# blank.net
KiCad netlist of a schematic drawn in EAGLE
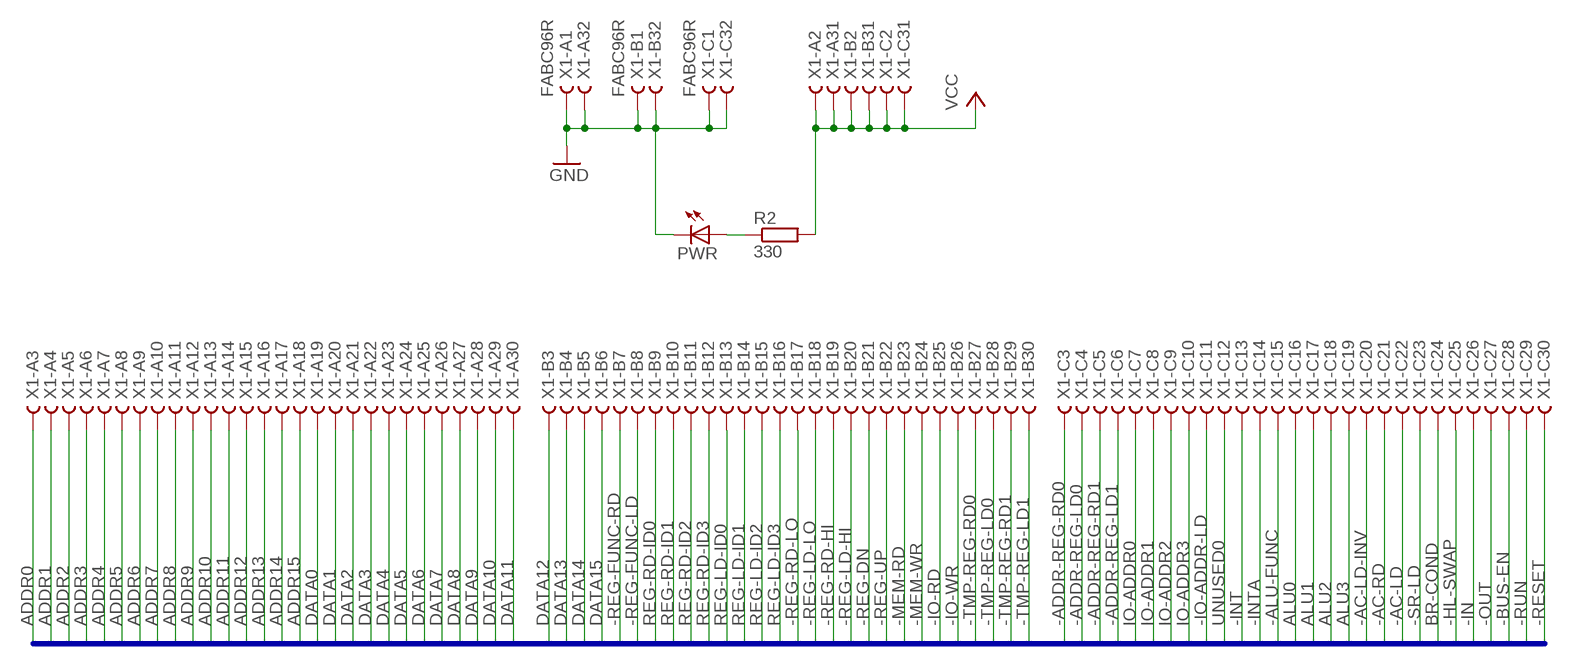
[diagram p0: schematic, sheet 1]

(export (version "E")
  (design (tool "Eeschema 10.0.6"))
  (components
    (comp (ref "PWR")
      (value "LED5MM")
      (footprint "eagle-import:LED5MM")
      (libsource (lib "eagle-import") (part "LED5MM"))
    )
    (comp (ref "R2")
      (value "330")
      (footprint "eagle-import:0207_10")
      (libsource (lib "eagle-import") (part "R0207/10"))
    )
    (comp (ref "X1")
      (value "FABC96R")
      (footprint "eagle-import:FABC96R")
      (libsource (lib "eagle-import") (part "FABC96R"))
    )
  )
  (nets
    (net (code "1") (name "/-AC-LD") (class "Default")
      (node (ref "X1") (pin "C22") (pinfunction "B_C22") (pintype "passive"))
    )
    (net (code "2") (name "/-AC-LD-INV") (class "Default")
      (node (ref "X1") (pin "C20") (pinfunction "B_C20") (pintype "passive"))
    )
    (net (code "3") (name "/-AC-RD") (class "Default")
      (node (ref "X1") (pin "C21") (pinfunction "B_C21") (pintype "passive"))
    )
    (net (code "4") (name "/-ADDR-REG-LD0") (class "Default")
      (node (ref "X1") (pin "C4") (pinfunction "B_C4") (pintype "passive"))
    )
    (net (code "5") (name "/-ADDR-REG-LD1") (class "Default")
      (node (ref "X1") (pin "C6") (pinfunction "B_C6") (pintype "passive"))
    )
    (net (code "6") (name "/-ADDR-REG-RD0") (class "Default")
      (node (ref "X1") (pin "C3") (pinfunction "B_C3") (pintype "passive"))
    )
    (net (code "7") (name "/-ADDR-REG-RD1") (class "Default")
      (node (ref "X1") (pin "C5") (pinfunction "B_C5") (pintype "passive"))
    )
    (net (code "8") (name "/-ALU-FUNC") (class "Default")
      (node (ref "X1") (pin "C15") (pinfunction "B_C15") (pintype "passive"))
    )
    (net (code "9") (name "/-BUS-EN") (class "Default")
      (node (ref "X1") (pin "C28") (pinfunction "B_C28") (pintype "passive"))
    )
    (net (code "10") (name "/-HL-SWAP") (class "Default")
      (node (ref "X1") (pin "C25") (pinfunction "B_C25") (pintype "passive"))
    )
    (net (code "11") (name "/-IN") (class "Default")
      (node (ref "X1") (pin "C26") (pinfunction "B_C26") (pintype "passive"))
    )
    (net (code "12") (name "/-INT") (class "Default")
      (node (ref "X1") (pin "C13") (pinfunction "B_C13") (pintype "passive"))
    )
    (net (code "13") (name "/-INTA") (class "Default")
      (node (ref "X1") (pin "C14") (pinfunction "B_C14") (pintype "passive"))
    )
    (net (code "14") (name "/-IO-ADDR-LD") (class "Default")
      (node (ref "X1") (pin "C11") (pinfunction "B_C11") (pintype "passive"))
    )
    (net (code "15") (name "/-IO-RD") (class "Default")
      (node (ref "X1") (pin "B25") (pinfunction "B_B25") (pintype "passive"))
    )
    (net (code "16") (name "/-IO-WR") (class "Default")
      (node (ref "X1") (pin "B26") (pinfunction "B_B26") (pintype "passive"))
    )
    (net (code "17") (name "/-MEM-RD") (class "Default")
      (node (ref "X1") (pin "B23") (pinfunction "B_B23") (pintype "passive"))
    )
    (net (code "18") (name "/-MEM-WR") (class "Default")
      (node (ref "X1") (pin "B24") (pinfunction "B_B24") (pintype "passive"))
    )
    (net (code "19") (name "/-OUT") (class "Default")
      (node (ref "X1") (pin "C27") (pinfunction "B_C27") (pintype "passive"))
    )
    (net (code "20") (name "/-REG-DN") (class "Default")
      (node (ref "X1") (pin "B21") (pinfunction "B_B21") (pintype "passive"))
    )
    (net (code "21") (name "/-REG-FUNC-LD") (class "Default")
      (node (ref "X1") (pin "B8") (pinfunction "B_B8") (pintype "passive"))
    )
    (net (code "22") (name "/-REG-FUNC-RD") (class "Default")
      (node (ref "X1") (pin "B7") (pinfunction "B_B7") (pintype "passive"))
    )
    (net (code "23") (name "/-REG-LD-HI") (class "Default")
      (node (ref "X1") (pin "B20") (pinfunction "B_B20") (pintype "passive"))
    )
    (net (code "24") (name "/-REG-LD-LO") (class "Default")
      (node (ref "X1") (pin "B18") (pinfunction "B_B18") (pintype "passive"))
    )
    (net (code "25") (name "/-REG-RD-HI") (class "Default")
      (node (ref "X1") (pin "B19") (pinfunction "B_B19") (pintype "passive"))
    )
    (net (code "26") (name "/-REG-RD-LO") (class "Default")
      (node (ref "X1") (pin "B17") (pinfunction "B_B17") (pintype "passive"))
    )
    (net (code "27") (name "/-REG-UP") (class "Default")
      (node (ref "X1") (pin "B22") (pinfunction "B_B22") (pintype "passive"))
    )
    (net (code "28") (name "/-RESET") (class "Default")
      (node (ref "X1") (pin "C30") (pinfunction "B_C30") (pintype "passive"))
    )
    (net (code "29") (name "/-RUN") (class "Default")
      (node (ref "X1") (pin "C29") (pinfunction "B_C29") (pintype "passive"))
    )
    (net (code "30") (name "/-SR-LD") (class "Default")
      (node (ref "X1") (pin "C23") (pinfunction "B_C23") (pintype "passive"))
    )
    (net (code "31") (name "/-TMP-REG-LD0") (class "Default")
      (node (ref "X1") (pin "B28") (pinfunction "B_B28") (pintype "passive"))
    )
    (net (code "32") (name "/-TMP-REG-LD1") (class "Default")
      (node (ref "X1") (pin "B30") (pinfunction "B_B30") (pintype "passive"))
    )
    (net (code "33") (name "/-TMP-REG-RD0") (class "Default")
      (node (ref "X1") (pin "B27") (pinfunction "B_B27") (pintype "passive"))
    )
    (net (code "34") (name "/-TMP-REG-RD1") (class "Default")
      (node (ref "X1") (pin "B29") (pinfunction "B_B29") (pintype "passive"))
    )
    (net (code "35") (name "/ADDR0") (class "Default")
      (node (ref "X1") (pin "A3") (pinfunction "B_A3") (pintype "passive"))
    )
    (net (code "36") (name "/ADDR1") (class "Default")
      (node (ref "X1") (pin "A4") (pinfunction "B_A4") (pintype "passive"))
    )
    (net (code "37") (name "/ADDR2") (class "Default")
      (node (ref "X1") (pin "A5") (pinfunction "B_A5") (pintype "passive"))
    )
    (net (code "38") (name "/ADDR3") (class "Default")
      (node (ref "X1") (pin "A6") (pinfunction "B_A6") (pintype "passive"))
    )
    (net (code "39") (name "/ADDR4") (class "Default")
      (node (ref "X1") (pin "A7") (pinfunction "B_A7") (pintype "passive"))
    )
    (net (code "40") (name "/ADDR5") (class "Default")
      (node (ref "X1") (pin "A8") (pinfunction "B_A8") (pintype "passive"))
    )
    (net (code "41") (name "/ADDR6") (class "Default")
      (node (ref "X1") (pin "A9") (pinfunction "B_A9") (pintype "passive"))
    )
    (net (code "42") (name "/ADDR7") (class "Default")
      (node (ref "X1") (pin "A10") (pinfunction "B_A10") (pintype "passive"))
    )
    (net (code "43") (name "/ADDR8") (class "Default")
      (node (ref "X1") (pin "A11") (pinfunction "B_A11") (pintype "passive"))
    )
    (net (code "44") (name "/ADDR9") (class "Default")
      (node (ref "X1") (pin "A12") (pinfunction "B_A12") (pintype "passive"))
    )
    (net (code "45") (name "/ADDR10") (class "Default")
      (node (ref "X1") (pin "A13") (pinfunction "B_A13") (pintype "passive"))
    )
    (net (code "46") (name "/ADDR11") (class "Default")
      (node (ref "X1") (pin "A14") (pinfunction "B_A14") (pintype "passive"))
    )
    (net (code "47") (name "/ADDR12") (class "Default")
      (node (ref "X1") (pin "A15") (pinfunction "B_A15") (pintype "passive"))
    )
    (net (code "48") (name "/ADDR13") (class "Default")
      (node (ref "X1") (pin "A16") (pinfunction "B_A16") (pintype "passive"))
    )
    (net (code "49") (name "/ADDR14") (class "Default")
      (node (ref "X1") (pin "A17") (pinfunction "B_A17") (pintype "passive"))
    )
    (net (code "50") (name "/ADDR15") (class "Default")
      (node (ref "X1") (pin "A18") (pinfunction "B_A18") (pintype "passive"))
    )
    (net (code "51") (name "/ALU0") (class "Default")
      (node (ref "X1") (pin "C16") (pinfunction "B_C16") (pintype "passive"))
    )
    (net (code "52") (name "/ALU1") (class "Default")
      (node (ref "X1") (pin "C17") (pinfunction "B_C17") (pintype "passive"))
    )
    (net (code "53") (name "/ALU2") (class "Default")
      (node (ref "X1") (pin "C18") (pinfunction "B_C18") (pintype "passive"))
    )
    (net (code "54") (name "/ALU3") (class "Default")
      (node (ref "X1") (pin "C19") (pinfunction "B_C19") (pintype "passive"))
    )
    (net (code "55") (name "/BR-COND") (class "Default")
      (node (ref "X1") (pin "C24") (pinfunction "B_C24") (pintype "passive"))
    )
    (net (code "56") (name "/DATA0") (class "Default")
      (node (ref "X1") (pin "A19") (pinfunction "B_A19") (pintype "passive"))
    )
    (net (code "57") (name "/DATA1") (class "Default")
      (node (ref "X1") (pin "A20") (pinfunction "B_A20") (pintype "passive"))
    )
    (net (code "58") (name "/DATA2") (class "Default")
      (node (ref "X1") (pin "A21") (pinfunction "B_A21") (pintype "passive"))
    )
    (net (code "59") (name "/DATA3") (class "Default")
      (node (ref "X1") (pin "A22") (pinfunction "B_A22") (pintype "passive"))
    )
    (net (code "60") (name "/DATA4") (class "Default")
      (node (ref "X1") (pin "A23") (pinfunction "B_A23") (pintype "passive"))
    )
    (net (code "61") (name "/DATA5") (class "Default")
      (node (ref "X1") (pin "A24") (pinfunction "B_A24") (pintype "passive"))
    )
    (net (code "62") (name "/DATA6") (class "Default")
      (node (ref "X1") (pin "A25") (pinfunction "B_A25") (pintype "passive"))
    )
    (net (code "63") (name "/DATA7") (class "Default")
      (node (ref "X1") (pin "A26") (pinfunction "B_A26") (pintype "passive"))
    )
    (net (code "64") (name "/DATA8") (class "Default")
      (node (ref "X1") (pin "A27") (pinfunction "B_A27") (pintype "passive"))
    )
    (net (code "65") (name "/DATA9") (class "Default")
      (node (ref "X1") (pin "A28") (pinfunction "B_A28") (pintype "passive"))
    )
    (net (code "66") (name "/DATA10") (class "Default")
      (node (ref "X1") (pin "A29") (pinfunction "B_A29") (pintype "passive"))
    )
    (net (code "67") (name "/DATA11") (class "Default")
      (node (ref "X1") (pin "A30") (pinfunction "B_A30") (pintype "passive"))
    )
    (net (code "68") (name "/DATA12") (class "Default")
      (node (ref "X1") (pin "B3") (pinfunction "B_B3") (pintype "passive"))
    )
    (net (code "69") (name "/DATA13") (class "Default")
      (node (ref "X1") (pin "B4") (pinfunction "B_B4") (pintype "passive"))
    )
    (net (code "70") (name "/DATA14") (class "Default")
      (node (ref "X1") (pin "B5") (pinfunction "B_B5") (pintype "passive"))
    )
    (net (code "71") (name "/DATA15") (class "Default")
      (node (ref "X1") (pin "B6") (pinfunction "B_B6") (pintype "passive"))
    )
    (net (code "72") (name "/IO-ADDR0") (class "Default")
      (node (ref "X1") (pin "C7") (pinfunction "B_C7") (pintype "passive"))
    )
    (net (code "73") (name "/IO-ADDR1") (class "Default")
      (node (ref "X1") (pin "C8") (pinfunction "B_C8") (pintype "passive"))
    )
    (net (code "74") (name "/IO-ADDR2") (class "Default")
      (node (ref "X1") (pin "C9") (pinfunction "B_C9") (pintype "passive"))
    )
    (net (code "75") (name "/IO-ADDR3") (class "Default")
      (node (ref "X1") (pin "C10") (pinfunction "B_C10") (pintype "passive"))
    )
    (net (code "76") (name "/REG-LD-ID0") (class "Default")
      (node (ref "X1") (pin "B13") (pinfunction "B_B13") (pintype "passive"))
    )
    (net (code "77") (name "/REG-LD-ID1") (class "Default")
      (node (ref "X1") (pin "B14") (pinfunction "B_B14") (pintype "passive"))
    )
    (net (code "78") (name "/REG-LD-ID2") (class "Default")
      (node (ref "X1") (pin "B15") (pinfunction "B_B15") (pintype "passive"))
    )
    (net (code "79") (name "/REG-LD-ID3") (class "Default")
      (node (ref "X1") (pin "B16") (pinfunction "B_B16") (pintype "passive"))
    )
    (net (code "80") (name "/REG-RD-ID0") (class "Default")
      (node (ref "X1") (pin "B9") (pinfunction "B_B9") (pintype "passive"))
    )
    (net (code "81") (name "/REG-RD-ID1") (class "Default")
      (node (ref "X1") (pin "B10") (pinfunction "B_B10") (pintype "passive"))
    )
    (net (code "82") (name "/REG-RD-ID2") (class "Default")
      (node (ref "X1") (pin "B11") (pinfunction "B_B11") (pintype "passive"))
    )
    (net (code "83") (name "/REG-RD-ID3") (class "Default")
      (node (ref "X1") (pin "B12") (pinfunction "B_B12") (pintype "passive"))
    )
    (net (code "84") (name "/UNUSED0") (class "Default")
      (node (ref "X1") (pin "C12") (pinfunction "B_C12") (pintype "passive"))
    )
    (net (code "85") (name "GND") (class "Default")
      (node (ref "PWR") (pin "K") (pinfunction "C_K") (pintype "passive"))
      (node (ref "X1") (pin "A1") (pinfunction "B_A1") (pintype "passive"))
      (node (ref "X1") (pin "A32") (pinfunction "B_A32") (pintype "passive"))
      (node (ref "X1") (pin "B1") (pinfunction "B_B1") (pintype "passive"))
      (node (ref "X1") (pin "B32") (pinfunction "B_B32") (pintype "passive"))
      (node (ref "X1") (pin "C1") (pinfunction "B_C1") (pintype "passive"))
      (node (ref "X1") (pin "C32") (pinfunction "B_C32") (pintype "passive"))
    )
    (net (code "86") (name "Net-(PWR-PadA)") (class "Default")
      (node (ref "PWR") (pin "A") (pinfunction "A_A") (pintype "passive"))
      (node (ref "R2") (pin "1") (pinfunction "1_1") (pintype "passive"))
    )
    (net (code "87") (name "VCC") (class "Default")
      (node (ref "R2") (pin "2") (pinfunction "2_2") (pintype "passive"))
      (node (ref "X1") (pin "A2") (pinfunction "B_A2") (pintype "passive"))
      (node (ref "X1") (pin "A31") (pinfunction "B_A31") (pintype "passive"))
      (node (ref "X1") (pin "B2") (pinfunction "B_B2") (pintype "passive"))
      (node (ref "X1") (pin "B31") (pinfunction "B_B31") (pintype "passive"))
      (node (ref "X1") (pin "C2") (pinfunction "B_C2") (pintype "passive"))
      (node (ref "X1") (pin "C31") (pinfunction "B_C31") (pintype "passive"))
    )
  )
)
